# one_Mhz.net
KiCad netlist of a schematic drawn in EAGLE
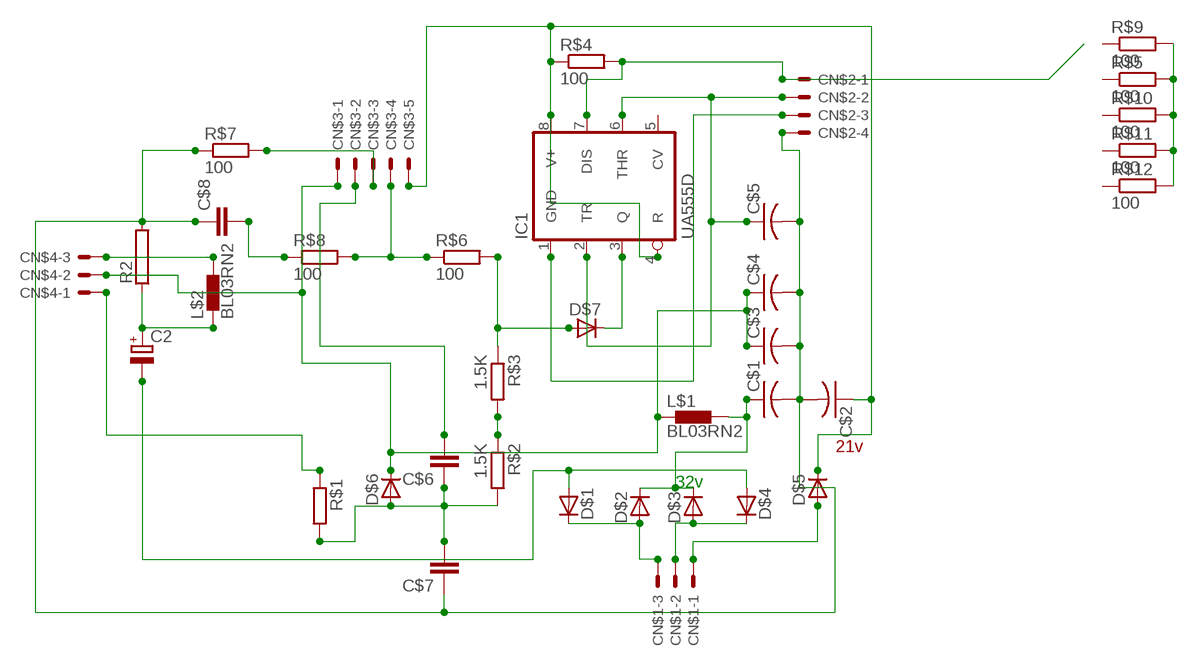
[diagram p0: schematic, sheet 1]

(export (version "E")
  (design (tool "Eeschema 10.0.6"))
  (components
    (comp (ref "C$1")
      (value "C-US050-075X075")
      (footprint "eagle-import:C050-075X075")
      (libsource (lib "eagle-import") (part "C-US050-075X075"))
    )
    (comp (ref "C$2")
      (value "C-US050-075X075")
      (footprint "eagle-import:C050-075X075")
      (libsource (lib "eagle-import") (part "C-US050-075X075"))
    )
    (comp (ref "C$3")
      (value "C-US025-050X050")
      (footprint "eagle-import:C025-050X050")
      (libsource (lib "eagle-import") (part "C-US025-050X050"))
    )
    (comp (ref "C$4")
      (value "C-US025-050X050")
      (footprint "eagle-import:C025-050X050")
      (libsource (lib "eagle-import") (part "C-US025-050X050"))
    )
    (comp (ref "C$5")
      (value "C-US025-050X050")
      (footprint "eagle-import:C025-050X050")
      (libsource (lib "eagle-import") (part "C-US025-050X050"))
    )
    (comp (ref "C$6")
      (value "C7.5/3")
      (footprint "eagle-import:C7.5B3")
      (libsource (lib "eagle-import") (part "C7.5/3"))
    )
    (comp (ref "C$7")
      (value "C7.5/3")
      (footprint "eagle-import:C7.5B3")
      (libsource (lib "eagle-import") (part "C7.5/3"))
    )
    (comp (ref "C$8")
      (value "C2.5/5")
      (footprint "eagle-import:C2.5-5")
      (libsource (lib "eagle-import") (part "C2.5/5"))
    )
    (comp (ref "C2")
      (value "CPOL-EUSANYO_H")
      (footprint "eagle-import:SANYO-OSCON_H")
      (libsource (lib "eagle-import") (part "CPOL-EUSANYO_H"))
    )
    (comp (ref "CN$1")
      (value "KK-156-3")
      (footprint "eagle-import:KK-156-3")
      (libsource (lib "eagle-import") (part "KK-156-3"))
    )
    (comp (ref "CN$2")
      (value "KK-156-4")
      (footprint "eagle-import:KK-156-4")
      (libsource (lib "eagle-import") (part "KK-156-4"))
    )
    (comp (ref "CN$3")
      (value "KK-156-5")
      (footprint "eagle-import:KK-156-5")
      (libsource (lib "eagle-import") (part "KK-156-5"))
    )
    (comp (ref "CN$4")
      (value "KK-156-3")
      (footprint "eagle-import:KK-156-3")
      (libsource (lib "eagle-import") (part "KK-156-3"))
    )
    (comp (ref "D$1")
      (value "D-SOD-87")
      (footprint "eagle-import:SOD87")
      (libsource (lib "eagle-import") (part "D-SOD-87"))
    )
    (comp (ref "D$2")
      (value "D-SOD-87")
      (footprint "eagle-import:SOD87")
      (libsource (lib "eagle-import") (part "D-SOD-87"))
    )
    (comp (ref "D$3")
      (value "D-SOD-87")
      (footprint "eagle-import:SOD87")
      (libsource (lib "eagle-import") (part "D-SOD-87"))
    )
    (comp (ref "D$4")
      (value "D-SOD-87")
      (footprint "eagle-import:SOD87")
      (libsource (lib "eagle-import") (part "D-SOD-87"))
    )
    (comp (ref "D$5")
      (value "D-SOD-87")
      (footprint "eagle-import:SOD87")
      (libsource (lib "eagle-import") (part "D-SOD-87"))
    )
    (comp (ref "D$6")
      (value "D-SOD-87")
      (footprint "eagle-import:SOD87")
      (libsource (lib "eagle-import") (part "D-SOD-87"))
    )
    (comp (ref "D$7")
      (value "D-SOD-87")
      (footprint "eagle-import:SOD87")
      (libsource (lib "eagle-import") (part "D-SOD-87"))
    )
    (comp (ref "IC1")
      (value "UA555D")
      (footprint "eagle-import:SO08")
      (libsource (lib "eagle-import") (part "555DUA"))
    )
    (comp (ref "L$1")
      (value "BL03RN2")
      (footprint "eagle-import:BL03RN2")
      (libsource (lib "eagle-import") (part "BL03RN2"))
    )
    (comp (ref "L$2")
      (value "BL03RN2")
      (footprint "eagle-import:BL03RN2")
      (libsource (lib "eagle-import") (part "BL03RN2"))
    )
    (comp (ref "R$1")
      (value "R-EU_R0603")
      (footprint "eagle-import:R0603")
      (libsource (lib "eagle-import") (part "R-EU_R0603"))
    )
    (comp (ref "R$2")
      (value "1.5K")
      (footprint "eagle-import:R0603")
      (libsource (lib "eagle-import") (part "R-EU_R0603"))
    )
    (comp (ref "R$3")
      (value "1.5K")
      (footprint "eagle-import:R0603")
      (libsource (lib "eagle-import") (part "R-EU_R0603"))
    )
    (comp (ref "R$4")
      (value "100")
      (footprint "eagle-import:R0603")
      (libsource (lib "eagle-import") (part "R-EU_R0603"))
    )
    (comp (ref "R$5")
      (value "100")
      (footprint "eagle-import:R0603")
      (libsource (lib "eagle-import") (part "R-EU_R0603"))
    )
    (comp (ref "R$6")
      (value "100")
      (footprint "eagle-import:R0603")
      (libsource (lib "eagle-import") (part "R-EU_R0603"))
    )
    (comp (ref "R$7")
      (value "100")
      (footprint "eagle-import:R0603")
      (libsource (lib "eagle-import") (part "R-EU_R0603"))
    )
    (comp (ref "R$8")
      (value "100")
      (footprint "eagle-import:R0603")
      (libsource (lib "eagle-import") (part "R-EU_R0603"))
    )
    (comp (ref "R$9")
      (value "100")
      (footprint "eagle-import:R0603")
      (libsource (lib "eagle-import") (part "R-EU_R0603"))
    )
    (comp (ref "R$10")
      (value "100")
      (footprint "eagle-import:R0603")
      (libsource (lib "eagle-import") (part "R-EU_R0603"))
    )
    (comp (ref "R$11")
      (value "100")
      (footprint "eagle-import:R0603")
      (libsource (lib "eagle-import") (part "R-EU_R0603"))
    )
    (comp (ref "R$12")
      (value "100")
      (footprint "eagle-import:R0603")
      (libsource (lib "eagle-import") (part "R-EU_R0603"))
    )
    (comp (ref "R2")
      (value "RAC01")
      (footprint "eagle-import:AC01")
      (libsource (lib "eagle-import") (part "RAC01"))
    )
  )
  (nets
    (net (code "1") (name "Net-(C$8-Pad2)") (class "Default")
      (node (ref "C$8") (pin "2") (pinfunction "2_2") (pintype "passive"))
      (node (ref "R$8") (pin "1") (pinfunction "1_1") (pintype "passive"))
    )
    (net (code "2") (name "Net-(C2-Pad+)") (class "Default")
      (node (ref "C2") (pin "+") (pinfunction "+_+") (pintype "passive"))
      (node (ref "L$2") (pin "1") (pinfunction "1_1") (pintype "passive"))
      (node (ref "R2") (pin "1") (pinfunction "1_1") (pintype "passive"))
    )
    (net (code "3") (name "Net-(CN$1A-S)") (class "Default")
      (node (ref "CN$1") (pin "1") (pinfunction "S_1") (pintype "passive"))
      (node (ref "D$5") (pin "2") (pinfunction "A_2") (pintype "passive"))
    )
    (net (code "4") (name "Net-(CN$1B-S)") (class "Default")
      (node (ref "CN$1") (pin "2") (pinfunction "S_2") (pintype "passive"))
      (node (ref "D$3") (pin "2") (pinfunction "A_2") (pintype "passive"))
      (node (ref "D$4") (pin "1") (pinfunction "C_1") (pintype "passive"))
    )
    (net (code "5") (name "Net-(CN$1C-S)") (class "Default")
      (node (ref "CN$1") (pin "3") (pinfunction "S_3") (pintype "passive"))
      (node (ref "D$1") (pin "1") (pinfunction "C_1") (pintype "passive"))
      (node (ref "D$2") (pin "2") (pinfunction "A_2") (pintype "passive"))
    )
    (net (code "6") (name "Net-(CN$2A-S)") (class "Default")
      (node (ref "CN$2") (pin "1") (pinfunction "S_1") (pintype "passive"))
      (node (ref "IC1") (pin "7") (pinfunction "DIS_7") (pintype "input"))
      (node (ref "R$4") (pin "2") (pinfunction "2_2") (pintype "passive"))
    )
    (net (code "7") (name "Net-(CN$2B-S)") (class "Default")
      (node (ref "C$5") (pin "1") (pinfunction "1_1") (pintype "passive"))
      (node (ref "CN$2") (pin "2") (pinfunction "S_2") (pintype "passive"))
      (node (ref "IC1") (pin "2") (pinfunction "TR_2") (pintype "input"))
      (node (ref "IC1") (pin "6") (pinfunction "THR_6") (pintype "input"))
    )
    (net (code "8") (name "Net-(CN$2C-S)") (class "Default")
      (node (ref "CN$2") (pin "3") (pinfunction "S_3") (pintype "passive"))
      (node (ref "IC1") (pin "1") (pinfunction "GND_1") (pintype "power_in"))
    )
    (net (code "9") (name "Net-(CN$2D-S)") (class "Default")
      (node (ref "C$1") (pin "2") (pinfunction "2_2") (pintype "passive"))
      (node (ref "C$2") (pin "2") (pinfunction "2_2") (pintype "passive"))
      (node (ref "C$3") (pin "2") (pinfunction "2_2") (pintype "passive"))
      (node (ref "C$4") (pin "2") (pinfunction "2_2") (pintype "passive"))
      (node (ref "C$5") (pin "2") (pinfunction "2_2") (pintype "passive"))
      (node (ref "C$7") (pin "1") (pinfunction "1_1") (pintype "passive"))
      (node (ref "C$8") (pin "1") (pinfunction "1_1") (pintype "passive"))
      (node (ref "CN$2") (pin "4") (pinfunction "S_4") (pintype "passive"))
      (node (ref "R$7") (pin "1") (pinfunction "1_1") (pintype "passive"))
      (node (ref "R2") (pin "2") (pinfunction "2_2") (pintype "passive"))
    )
    (net (code "10") (name "Net-(CN$3A-S)") (class "Default")
      (node (ref "C$3") (pin "1") (pinfunction "1_1") (pintype "passive"))
      (node (ref "C$4") (pin "1") (pinfunction "1_1") (pintype "passive"))
      (node (ref "CN$3") (pin "1") (pinfunction "S_1") (pintype "passive"))
      (node (ref "CN$4") (pin "2") (pinfunction "S_2") (pintype "passive"))
      (node (ref "D$6") (pin "1") (pinfunction "C_1") (pintype "passive"))
      (node (ref "L$1") (pin "1") (pinfunction "1_1") (pintype "passive"))
    )
    (net (code "11") (name "Net-(CN$3B-S)") (class "Default")
      (node (ref "C$6") (pin "2") (pinfunction "2_2") (pintype "passive"))
      (node (ref "CN$3") (pin "2") (pinfunction "S_2") (pintype "passive"))
    )
    (net (code "12") (name "Net-(CN$3C-S)") (class "Default")
      (node (ref "CN$3") (pin "3") (pinfunction "S_3") (pintype "passive"))
      (node (ref "R$7") (pin "2") (pinfunction "2_2") (pintype "passive"))
    )
    (net (code "13") (name "Net-(CN$3D-S)") (class "Default")
      (node (ref "CN$3") (pin "4") (pinfunction "S_4") (pintype "passive"))
      (node (ref "R$6") (pin "1") (pinfunction "1_1") (pintype "passive"))
      (node (ref "R$8") (pin "2") (pinfunction "2_2") (pintype "passive"))
    )
    (net (code "14") (name "Net-(CN$3E-S)") (class "Default")
      (node (ref "C$2") (pin "1") (pinfunction "1_1") (pintype "passive"))
      (node (ref "CN$3") (pin "5") (pinfunction "S_5") (pintype "passive"))
      (node (ref "D$5") (pin "1") (pinfunction "C_1") (pintype "passive"))
      (node (ref "IC1") (pin "4") (pinfunction "R_4") (pintype "input"))
      (node (ref "IC1") (pin "8") (pinfunction "V+_8") (pintype "power_in"))
      (node (ref "R$4") (pin "1") (pinfunction "1_1") (pintype "passive"))
    )
    (net (code "15") (name "Net-(CN$4A-S)") (class "Default")
      (node (ref "CN$4") (pin "1") (pinfunction "S_1") (pintype "passive"))
      (node (ref "R$1") (pin "1") (pinfunction "1_1") (pintype "passive"))
    )
    (net (code "16") (name "Net-(CN$4C-S)") (class "Default")
      (node (ref "CN$4") (pin "3") (pinfunction "S_3") (pintype "passive"))
      (node (ref "L$2") (pin "2") (pinfunction "2_2") (pintype "passive"))
    )
    (net (code "17") (name "Net-(D$1-A)") (class "Default")
      (node (ref "C2") (pin "-") (pinfunction "-_-") (pintype "passive"))
      (node (ref "D$1") (pin "2") (pinfunction "A_2") (pintype "passive"))
      (node (ref "D$4") (pin "2") (pinfunction "A_2") (pintype "passive"))
    )
    (net (code "18") (name "Net-(D$2-C)") (class "Default")
      (node (ref "C$1") (pin "1") (pinfunction "1_1") (pintype "passive"))
      (node (ref "D$2") (pin "1") (pinfunction "C_1") (pintype "passive"))
      (node (ref "D$3") (pin "1") (pinfunction "C_1") (pintype "passive"))
      (node (ref "L$1") (pin "2") (pinfunction "2_2") (pintype "passive"))
    )
    (net (code "19") (name "Net-(D$6-A)") (class "Default")
      (node (ref "C$6") (pin "1") (pinfunction "1_1") (pintype "passive"))
      (node (ref "C$7") (pin "2") (pinfunction "2_2") (pintype "passive"))
      (node (ref "D$6") (pin "2") (pinfunction "A_2") (pintype "passive"))
      (node (ref "R$1") (pin "2") (pinfunction "2_2") (pintype "passive"))
      (node (ref "R$2") (pin "2") (pinfunction "2_2") (pintype "passive"))
    )
    (net (code "20") (name "Net-(D$7-A)") (class "Default")
      (node (ref "D$7") (pin "2") (pinfunction "A_2") (pintype "passive"))
      (node (ref "R$3") (pin "1") (pinfunction "1_1") (pintype "passive"))
      (node (ref "R$6") (pin "2") (pinfunction "2_2") (pintype "passive"))
    )
    (net (code "21") (name "Net-(D$7-C)") (class "Default")
      (node (ref "D$7") (pin "1") (pinfunction "C_1") (pintype "passive"))
      (node (ref "IC1") (pin "3") (pinfunction "Q_3") (pintype "output"))
    )
    (net (code "22") (name "Net-(R$2-Pad1)") (class "Default")
      (node (ref "R$2") (pin "1") (pinfunction "1_1") (pintype "passive"))
      (node (ref "R$3") (pin "2") (pinfunction "2_2") (pintype "passive"))
    )
    (net (code "23") (name "Net-(R$10-Pad2)") (class "Default")
      (node (ref "R$10") (pin "2") (pinfunction "2_2") (pintype "passive"))
      (node (ref "R$11") (pin "2") (pinfunction "2_2") (pintype "passive"))
      (node (ref "R$12") (pin "2") (pinfunction "2_2") (pintype "passive"))
      (node (ref "R$5") (pin "2") (pinfunction "2_2") (pintype "passive"))
      (node (ref "R$9") (pin "2") (pinfunction "2_2") (pintype "passive"))
    )
    (net (code "24") (name "unconnected-(IC1-CV-Pad5)") (class "Default")
      (node (ref "IC1") (pin "5") (pinfunction "CV_5") (pintype "input"))
    )
    (net (code "25") (name "unconnected-(R$5-Pad1)") (class "Default")
      (node (ref "R$5") (pin "1") (pinfunction "1_1") (pintype "passive"))
    )
    (net (code "26") (name "unconnected-(R$9-Pad1)") (class "Default")
      (node (ref "R$9") (pin "1") (pinfunction "1_1") (pintype "passive"))
    )
    (net (code "27") (name "unconnected-(R$10-Pad1)") (class "Default")
      (node (ref "R$10") (pin "1") (pinfunction "1_1") (pintype "passive"))
    )
    (net (code "28") (name "unconnected-(R$11-Pad1)") (class "Default")
      (node (ref "R$11") (pin "1") (pinfunction "1_1") (pintype "passive"))
    )
    (net (code "29") (name "unconnected-(R$12-Pad1)") (class "Default")
      (node (ref "R$12") (pin "1") (pinfunction "1_1") (pintype "passive"))
    )
  )
)
